# sensor_v20.net
KiCad netlist of a schematic drawn in EAGLE
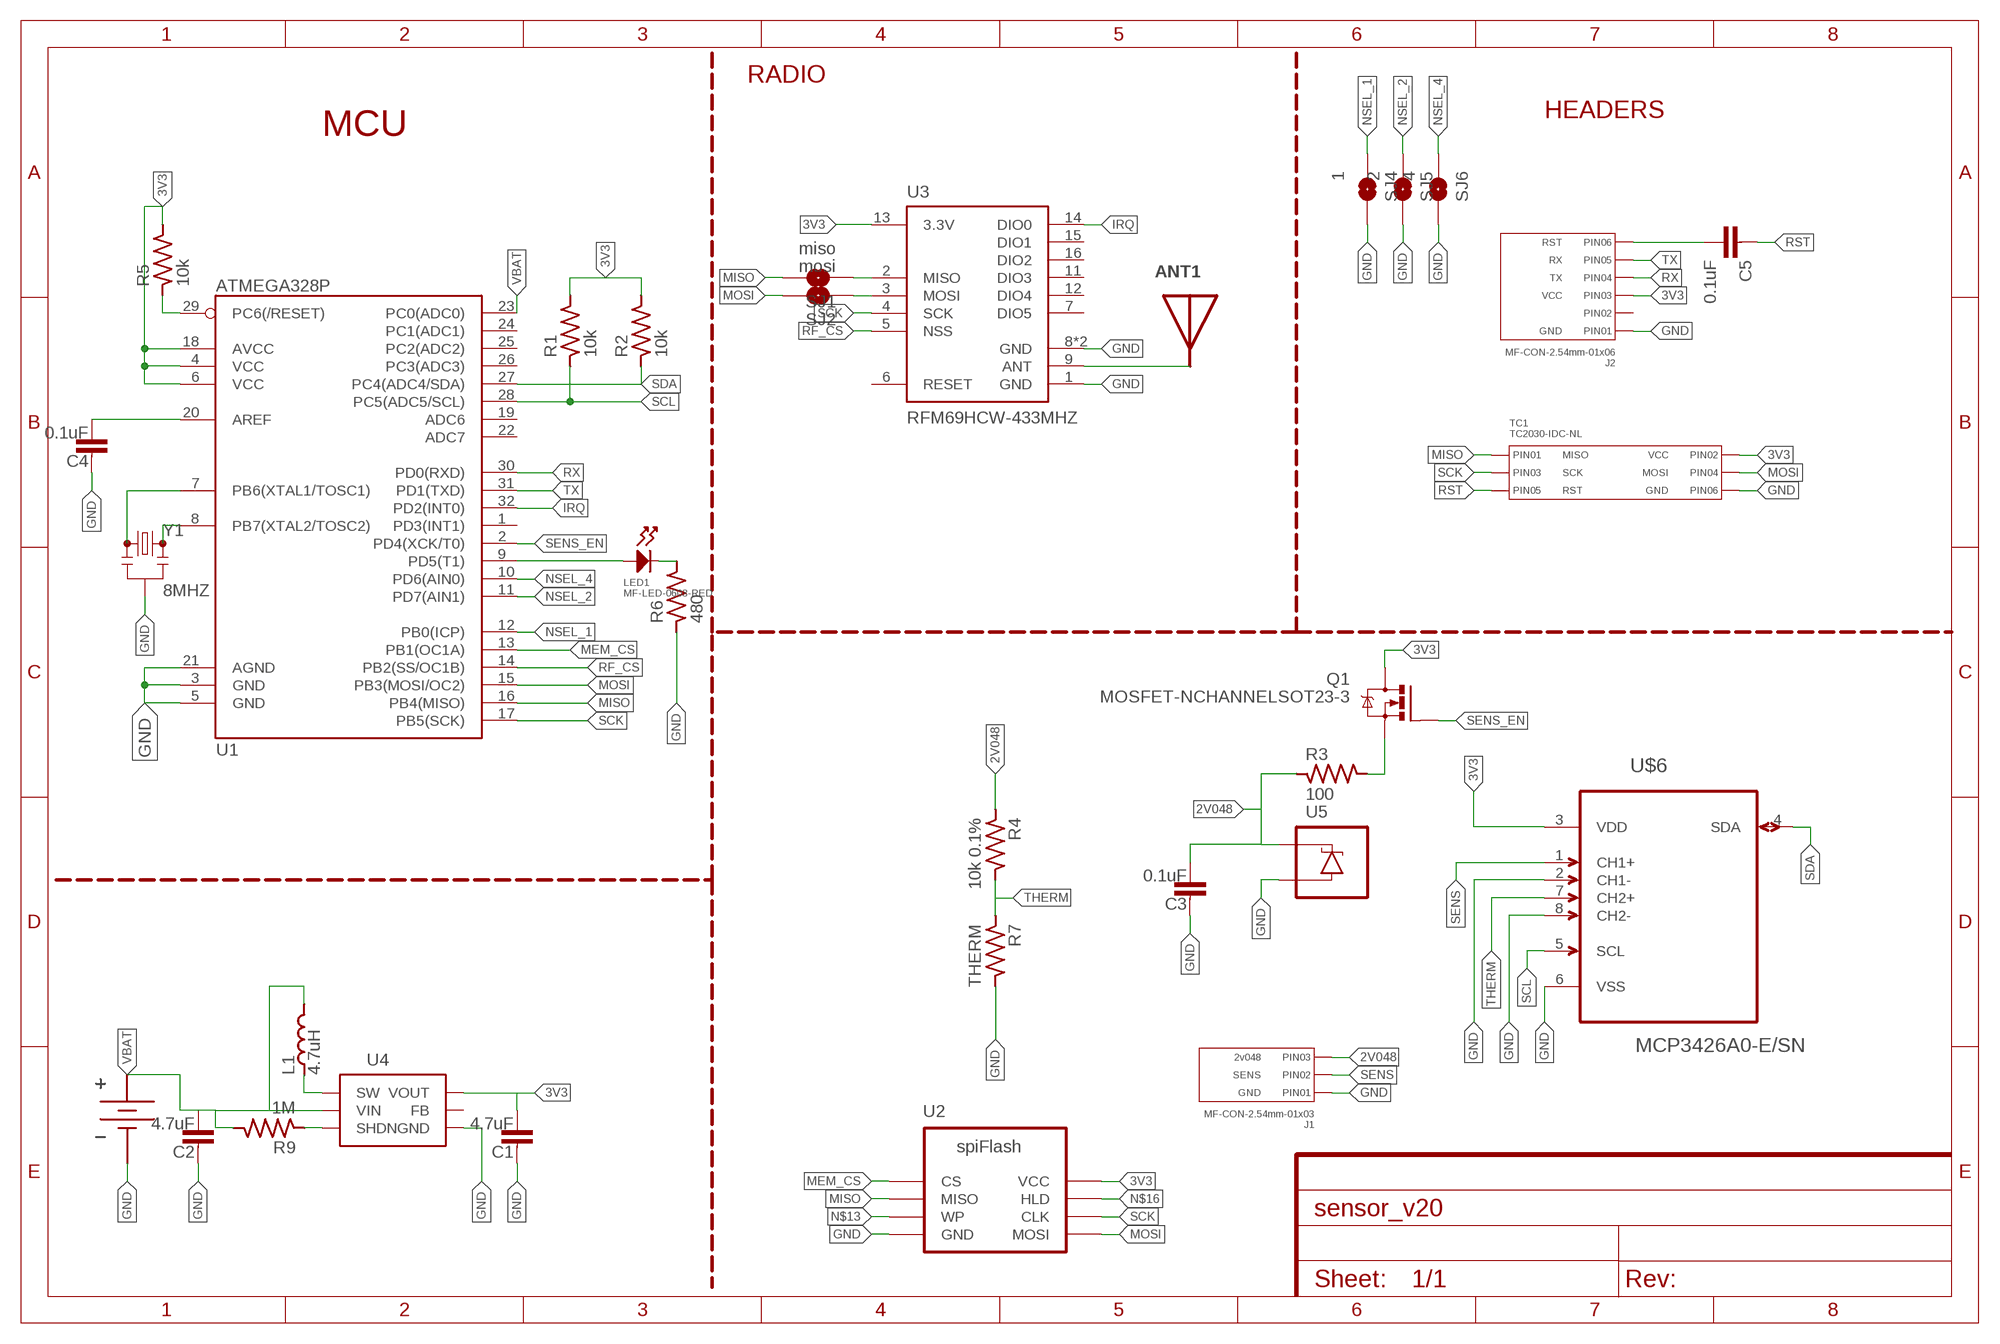
[diagram p0: schematic, sheet 1]

(export (version "E")
  (design (tool "Eeschema 10.0.6"))
  (components
    (comp (ref "ANT1")
      (value "ANTENNA-433_CHIP")
      (footprint "eagle-import:ANT_433_CHIP")
      (fields (field (name "PARTNO") "0433AT62A0020E"))
      (libsource (lib "eagle-import") (part "ANTENNA-433_CHIP"))
    )
    (comp (ref "C1")
      (value "4.7uF")
      (footprint "eagle-import:C0603-N")
      (libsource (lib "eagle-import") (part "CAPACITOR_NP0603-N"))
    )
    (comp (ref "C2")
      (value "4.7uF")
      (footprint "eagle-import:C0603-N")
      (libsource (lib "eagle-import") (part "CAPACITOR_NP0603-N"))
    )
    (comp (ref "C3")
      (value "0.1uF")
      (footprint "eagle-import:C0603-N")
      (libsource (lib "eagle-import") (part "CAPACITOR_NP0603-N"))
    )
    (comp (ref "C4")
      (value "0.1uF")
      (footprint "eagle-import:C0603-N")
      (libsource (lib "eagle-import") (part "CAPACITOR_NP0603-N"))
    )
    (comp (ref "C5")
      (value "0.1uF")
      (footprint "eagle-import:C0603-N")
      (libsource (lib "eagle-import") (part "CAPACITOR0603-N"))
    )
    (comp (ref "J1")
      (value "MF-CON-2.54mm-01x03")
      (footprint "eagle-import:PTH_2.54MM_01X03")
      (fields
        (field (name "HOUSEPART") "YES")
        (field (name "LABEL01") "GND")
        (field (name "LABEL02") "SENS")
        (field (name "LABEL03") "2v048")
        (field (name "PARTNO") "0022053031")
      )
      (libsource (lib "eagle-import") (part "CON_01X03_PTH_2.54MM"))
    )
    (comp (ref "J2")
      (value "MF-CON-2.54mm-01x06")
      (footprint "eagle-import:PTH_2.54MM_01X06")
      (fields
        (field (name "HOUSEPART") "YES")
        (field (name "LABEL01") "GND")
        (field (name "LABEL03") "VCC")
        (field (name "LABEL04") "TX")
        (field (name "LABEL05") "RX")
        (field (name "LABEL06") "RST")
      )
      (libsource (lib "eagle-import") (part "CON_01X06_PTH_2.54MM"))
    )
    (comp (ref "L1")
      (value "4.7uH")
      (footprint "eagle-import:L3030")
      (libsource (lib "eagle-import") (part "INDUCTOR3030"))
    )
    (comp (ref "LED1")
      (value "MF-LED-0603-RED")
      (footprint "eagle-import:LED0603")
      (fields (field (name "HOUSEPART") "YES"))
      (libsource (lib "eagle-import") (part "LED_SINGLE-0603-RED"))
    )
    (comp (ref "Q1")
      (value "MOSFET-NCHANNELSOT23-3")
      (footprint "eagle-import:SOT23-3")
      (libsource (lib "eagle-import") (part "MOSFET-NCHANNELSOT23-3"))
    )
    (comp (ref "R1")
      (value "10k")
      (footprint "eagle-import:R0603-N")
      (libsource (lib "eagle-import") (part "RESISTOR0603-N"))
    )
    (comp (ref "R2")
      (value "10k")
      (footprint "eagle-import:R0603-N")
      (libsource (lib "eagle-import") (part "RESISTOR0603-N"))
    )
    (comp (ref "R3")
      (value "100")
      (footprint "eagle-import:R0603-N")
      (libsource (lib "eagle-import") (part "RESISTOR0603-N"))
    )
    (comp (ref "R4")
      (value "10k 0.1%")
      (footprint "eagle-import:R0603-N")
      (fields (field (name "PARTNO") "0.1% !!"))
      (libsource (lib "eagle-import") (part "RESISTOR0603-N"))
    )
    (comp (ref "R5")
      (value "10k")
      (footprint "eagle-import:R0603-N")
      (libsource (lib "eagle-import") (part "RESISTOR0603-N"))
    )
    (comp (ref "R6")
      (value "480")
      (footprint "eagle-import:R0603-N")
      (libsource (lib "eagle-import") (part "RESISTOR0603-N"))
    )
    (comp (ref "R7")
      (value "THERM")
      (footprint "eagle-import:R0603-N")
      (fields (field (name "PARTNO") "FIND PART!!"))
      (libsource (lib "eagle-import") (part "RESISTOR0603-N"))
    )
    (comp (ref "R9")
      (value "1M")
      (footprint "eagle-import:R0603-N")
      (libsource (lib "eagle-import") (part "RESISTOR0603-N"))
    )
    (comp (ref "SJ1")
      (value "miso")
      (footprint "eagle-import:SJ_2S-NOTRACE")
      (libsource (lib "eagle-import") (part "SOLDERJUMPERNC2"))
    )
    (comp (ref "SJ2")
      (value "mosi")
      (footprint "eagle-import:SJ_2S-NOTRACE")
      (libsource (lib "eagle-import") (part "SOLDERJUMPERNC2"))
    )
    (comp (ref "SJ4")
      (value "1")
      (footprint "eagle-import:SJ_2S-NOTRACE")
      (libsource (lib "eagle-import") (part "SOLDERJUMPERNC2"))
    )
    (comp (ref "SJ5")
      (value "2")
      (footprint "eagle-import:SJ_2S-NOTRACE")
      (libsource (lib "eagle-import") (part "SOLDERJUMPERNC2"))
    )
    (comp (ref "SJ6")
      (value "4")
      (footprint "eagle-import:SJ_2S-NOTRACE")
      (libsource (lib "eagle-import") (part "SOLDERJUMPERNC2"))
    )
    (comp (ref "TC1")
      (value "TC2030-IDC-NL")
      (footprint "eagle-import:TC2030-IDC-NL")
      (fields (field (name "HOUSEPART") "NO") (field (name "PARTNO") "NA"))
      (libsource (lib "eagle-import") (part "CON_02X03_TC2030-IDC-NL_AVRISP"))
    )
    (comp (ref "U$1")
      (value "KEYSTONEAAHOLDER_2CELL")
      (footprint "eagle-import:KEYSTONEAAHOLDER_2CELL")
      (libsource (lib "eagle-import") (part "KEYSTONEAAHOLDER_2CELL"))
    )
    (comp (ref "U$6")
      (value "MCP3426A0-E/SN")
      (footprint "eagle-import:SOIC127P600X175-8N")
      (libsource (lib "eagle-import") (part "MCP3426A0-E/SN"))
    )
    (comp (ref "U1")
      (value "ATMEGA328P")
      (footprint "eagle-import:TQFP32")
      (libsource (lib "eagle-import") (part "ATMEGA328P_SMD-AU"))
    )
    (comp (ref "U2")
      (value "WINBOND_FLASH_4MBIT-SOIC")
      (footprint "eagle-import:SOIC8")
      (libsource (lib "eagle-import") (part "WINBOND_FLASH_4MBIT-SOIC"))
    )
    (comp (ref "U3")
      (value "RFM69HCW-433MHZ")
      (footprint "eagle-import:RFM69HCW-XXXS2")
      (fields (field (name "PARTNO") "COM-13910"))
      (libsource (lib "eagle-import") (part "RFM69HCW-433MHZ"))
    )
    (comp (ref "U4")
      (value "AAT1217-SOT23-6")
      (footprint "eagle-import:SOT23-6")
      (fields (field (name "PARTNO") "AAT1217ICA-3.3-T1"))
      (libsource (lib "eagle-import") (part "AAT1217-SOT23-6"))
    )
    (comp (ref "U5")
      (value "LM4040-SOT-23-3")
      (footprint "eagle-import:SOT23-3")
      (fields (field (name "PARTNO") "LM4040AIM3-2.0/NOPB "))
      (libsource (lib "eagle-import") (part "LM4040-SOT-23-3"))
    )
    (comp (ref "Y1")
      (value "8MHZ")
      (footprint "eagle-import:RESONATOR-SMD")
      (fields (field (name "PARTNO") "CSTCE8M00G55-R0"))
      (libsource (lib "eagle-import") (part "RESONATOR8MHZ"))
    )
  )
  (nets
    (net (code "1") (name "2V048") (class "Default")
      (node (ref "C3") (pin "2") (pinfunction "2_2") (pintype "passive"))
      (node (ref "J1") (pin "P$3") (pinfunction "PIN3_P$3") (pintype "bidirectional"))
      (node (ref "R3") (pin "1") (pinfunction "P$1_1") (pintype "passive"))
      (node (ref "R4") (pin "1") (pinfunction "P$1_1") (pintype "passive"))
      (node (ref "U5") (pin "1") (pinfunction "C_1") (pintype "bidirectional"))
    )
    (net (code "2") (name "3V3") (class "Default")
      (node (ref "C1") (pin "2") (pinfunction "2_2") (pintype "passive"))
      (node (ref "J2") (pin "P$3") (pinfunction "PIN3_P$3") (pintype "bidirectional"))
      (node (ref "Q1") (pin "3") (pinfunction "D_3") (pintype "passive"))
      (node (ref "R1") (pin "2") (pinfunction "P$2_2") (pintype "passive"))
      (node (ref "R2") (pin "2") (pinfunction "P$2_2") (pintype "passive"))
      (node (ref "R5") (pin "2") (pinfunction "P$2_2") (pintype "passive"))
      (node (ref "TC1") (pin "P$2") (pinfunction "PIN2_P$2") (pintype "bidirectional"))
      (node (ref "U$6") (pin "3") (pinfunction "VDD_3") (pintype "power_in"))
      (node (ref "U1") (pin "18") (pinfunction "AVCC_18") (pintype "bidirectional"))
      (node (ref "U1") (pin "4") (pinfunction "VCC_4") (pintype "bidirectional"))
      (node (ref "U1") (pin "6") (pinfunction "VCC_6") (pintype "bidirectional"))
      (node (ref "U2") (pin "8") (pinfunction "VCC_8") (pintype "bidirectional"))
      (node (ref "U3") (pin "13") (pinfunction "3.3V_13") (pintype "power_in"))
      (node (ref "U4") (pin "5") (pinfunction "VOUT_5") (pintype "bidirectional"))
    )
    (net (code "3") (name "GND") (class "Default")
      (node (ref "C1") (pin "1") (pinfunction "1_1") (pintype "passive"))
      (node (ref "C2") (pin "1") (pinfunction "1_1") (pintype "passive"))
      (node (ref "C3") (pin "1") (pinfunction "1_1") (pintype "passive"))
      (node (ref "C4") (pin "1") (pinfunction "1_1") (pintype "passive"))
      (node (ref "J1") (pin "P$1") (pinfunction "PIN1_P$1") (pintype "bidirectional"))
      (node (ref "J2") (pin "P$1") (pinfunction "PIN1_P$1") (pintype "bidirectional"))
      (node (ref "R6") (pin "1") (pinfunction "P$1_1") (pintype "passive"))
      (node (ref "R7") (pin "2") (pinfunction "P$2_2") (pintype "passive"))
      (node (ref "SJ4") (pin "2") (pinfunction "2_2") (pintype "passive"))
      (node (ref "SJ5") (pin "2") (pinfunction "2_2") (pintype "passive"))
      (node (ref "SJ6") (pin "2") (pinfunction "2_2") (pintype "passive"))
      (node (ref "TC1") (pin "P$6") (pinfunction "PIN6_P$6") (pintype "bidirectional"))
      (node (ref "U$1") (pin "P$2") (pinfunction "GND_P$2") (pintype "bidirectional"))
      (node (ref "U$6") (pin "2") (pinfunction "CH1-_2") (pintype "input"))
      (node (ref "U$6") (pin "6") (pinfunction "VSS_6") (pintype "power_in"))
      (node (ref "U$6") (pin "8") (pinfunction "CH2-_8") (pintype "input"))
      (node (ref "U1") (pin "21") (pinfunction "AGND_21") (pintype "bidirectional"))
      (node (ref "U1") (pin "3") (pinfunction "GND_3") (pintype "bidirectional"))
      (node (ref "U1") (pin "5") (pinfunction "GND_5") (pintype "bidirectional"))
      (node (ref "U2") (pin "4") (pinfunction "GND_4") (pintype "bidirectional"))
      (node (ref "U3") (pin "1") (pinfunction "GND_1") (pintype "power_in"))
      (node (ref "U3") (pin "10") (pinfunction "GND_10") (pintype "power_in"))
      (node (ref "U3") (pin "8") (pinfunction "GND_8") (pintype "power_in"))
      (node (ref "U4") (pin "2") (pinfunction "GND_2") (pintype "bidirectional"))
      (node (ref "U5") (pin "2") (pinfunction "A_2") (pintype "bidirectional"))
      (node (ref "Y1") (pin "2") (pinfunction "2_2") (pintype "passive"))
    )
    (net (code "4") (name "IRQ") (class "Default")
      (node (ref "U1") (pin "32") (pinfunction "PD2(INT0)_32") (pintype "bidirectional"))
      (node (ref "U3") (pin "14") (pinfunction "DIO0_14") (pintype "bidirectional"))
    )
    (net (code "5") (name "MEM_CS") (class "Default")
      (node (ref "U1") (pin "13") (pinfunction "PB1(OC1A)_13") (pintype "bidirectional"))
      (node (ref "U2") (pin "1") (pinfunction "CS_1") (pintype "bidirectional"))
    )
    (net (code "6") (name "MISO") (class "Default")
      (node (ref "SJ1") (pin "2") (pinfunction "2_2") (pintype "passive"))
      (node (ref "TC1") (pin "P$1") (pinfunction "PIN1_P$1") (pintype "bidirectional"))
      (node (ref "U1") (pin "16") (pinfunction "PB4(MISO)_16") (pintype "bidirectional"))
      (node (ref "U2") (pin "2") (pinfunction "MISO_2") (pintype "bidirectional"))
    )
    (net (code "7") (name "MOSI") (class "Default")
      (node (ref "SJ2") (pin "2") (pinfunction "2_2") (pintype "passive"))
      (node (ref "TC1") (pin "P$4") (pinfunction "PIN4_P$4") (pintype "bidirectional"))
      (node (ref "U1") (pin "15") (pinfunction "PB3(MOSI/OC2)_15") (pintype "bidirectional"))
      (node (ref "U2") (pin "5") (pinfunction "MOSI_5") (pintype "bidirectional"))
    )
    (net (code "8") (name "N$13") (class "Default")
      (node (ref "U2") (pin "3") (pinfunction "WP_3") (pintype "bidirectional"))
    )
    (net (code "9") (name "N$16") (class "Default")
      (node (ref "U2") (pin "7") (pinfunction "HLD_7") (pintype "bidirectional"))
    )
    (net (code "10") (name "NSEL_1") (class "Default")
      (node (ref "SJ4") (pin "1") (pinfunction "1_1") (pintype "passive"))
      (node (ref "U1") (pin "12") (pinfunction "PB0(ICP)_12") (pintype "bidirectional"))
    )
    (net (code "11") (name "NSEL_2") (class "Default")
      (node (ref "SJ5") (pin "1") (pinfunction "1_1") (pintype "passive"))
      (node (ref "U1") (pin "11") (pinfunction "PD7(AIN1)_11") (pintype "bidirectional"))
    )
    (net (code "12") (name "NSEL_4") (class "Default")
      (node (ref "SJ6") (pin "1") (pinfunction "1_1") (pintype "passive"))
      (node (ref "U1") (pin "10") (pinfunction "PD6(AIN0)_10") (pintype "bidirectional"))
    )
    (net (code "13") (name "Net-(J2-PIN6)") (class "Default")
      (node (ref "C5") (pin "2") (pinfunction "2_2") (pintype "passive"))
      (node (ref "J2") (pin "P$6") (pinfunction "PIN6_P$6") (pintype "bidirectional"))
    )
    (net (code "14") (name "Net-(Q1-S)") (class "Default")
      (node (ref "Q1") (pin "2") (pinfunction "S_2") (pintype "passive"))
      (node (ref "R3") (pin "2") (pinfunction "P$2_2") (pintype "passive"))
    )
    (net (code "15") (name "Net-(R6-P$2)") (class "Default")
      (node (ref "LED1") (pin "CATHODE") (pinfunction "CATHODE_CATHODE") (pintype "power_in"))
      (node (ref "R6") (pin "2") (pinfunction "P$2_2") (pintype "passive"))
    )
    (net (code "16") (name "Net-(R9-P$1)") (class "Default")
      (node (ref "R9") (pin "1") (pinfunction "P$1_1") (pintype "passive"))
      (node (ref "U4") (pin "4") (pinfunction "SHDN_4") (pintype "bidirectional"))
    )
    (net (code "17") (name "Net-(U1-AREF)") (class "Default")
      (node (ref "C4") (pin "2") (pinfunction "2_2") (pintype "passive"))
      (node (ref "U1") (pin "20") (pinfunction "AREF_20") (pintype "bidirectional"))
    )
    (net (code "18") (name "Net-(U1-PB6(XTAL1{slash}TOSC1))") (class "Default")
      (node (ref "U1") (pin "7") (pinfunction "PB6(XTAL1/TOSC1)_7") (pintype "bidirectional"))
      (node (ref "Y1") (pin "1") (pinfunction "1_1") (pintype "passive"))
    )
    (net (code "19") (name "Net-(U1-PB7(XTAL2{slash}TOSC2))") (class "Default")
      (node (ref "U1") (pin "8") (pinfunction "PB7(XTAL2/TOSC2)_8") (pintype "bidirectional"))
      (node (ref "Y1") (pin "3") (pinfunction "3_3") (pintype "passive"))
    )
    (net (code "20") (name "Net-(U1-PD5(T1))") (class "Default")
      (node (ref "LED1") (pin "ANODE") (pinfunction "ANODE_ANODE") (pintype "power_in"))
      (node (ref "U1") (pin "9") (pinfunction "PD5(T1)_9") (pintype "bidirectional"))
    )
    (net (code "21") (name "Net-(U3-ANT)") (class "Default")
      (node (ref "ANT1") (pin "1") (pinfunction "1_1") (pintype "bidirectional"))
      (node (ref "U3") (pin "9") (pinfunction "ANT_9") (pintype "passive"))
    )
    (net (code "22") (name "Net-(U3-MISO)") (class "Default")
      (node (ref "SJ1") (pin "1") (pinfunction "1_1") (pintype "passive"))
      (node (ref "U3") (pin "2") (pinfunction "MISO_2") (pintype "bidirectional"))
    )
    (net (code "23") (name "Net-(U3-MOSI)") (class "Default")
      (node (ref "SJ2") (pin "1") (pinfunction "1_1") (pintype "passive"))
      (node (ref "U3") (pin "3") (pinfunction "MOSI_3") (pintype "input"))
    )
    (net (code "24") (name "Net-(U4-SW)") (class "Default")
      (node (ref "L1") (pin "P$1") (pinfunction "P$1_P$1") (pintype "passive"))
      (node (ref "U4") (pin "1") (pinfunction "SW_1") (pintype "bidirectional"))
    )
    (net (code "25") (name "RF_CS") (class "Default")
      (node (ref "U1") (pin "14") (pinfunction "PB2(SS/OC1B)_14") (pintype "bidirectional"))
      (node (ref "U3") (pin "5") (pinfunction "NSS_5") (pintype "input"))
    )
    (net (code "26") (name "RST") (class "Default")
      (node (ref "C5") (pin "1") (pinfunction "1_1") (pintype "passive"))
      (node (ref "R5") (pin "1") (pinfunction "P$1_1") (pintype "passive"))
      (node (ref "TC1") (pin "P$5") (pinfunction "PIN5_P$5") (pintype "bidirectional"))
      (node (ref "U1") (pin "29") (pinfunction "PC6(/RESET)_29") (pintype "bidirectional"))
    )
    (net (code "27") (name "RX") (class "Default")
      (node (ref "J2") (pin "P$4") (pinfunction "PIN4_P$4") (pintype "bidirectional"))
      (node (ref "U1") (pin "30") (pinfunction "PD0(RXD)_30") (pintype "bidirectional"))
    )
    (net (code "28") (name "SCK") (class "Default")
      (node (ref "TC1") (pin "P$3") (pinfunction "PIN3_P$3") (pintype "bidirectional"))
      (node (ref "U1") (pin "17") (pinfunction "PB5(SCK)_17") (pintype "bidirectional"))
      (node (ref "U2") (pin "6") (pinfunction "CLK_6") (pintype "bidirectional"))
      (node (ref "U3") (pin "4") (pinfunction "SCK_4") (pintype "input"))
    )
    (net (code "29") (name "SCL") (class "Default")
      (node (ref "R1") (pin "1") (pinfunction "P$1_1") (pintype "passive"))
      (node (ref "U$6") (pin "5") (pinfunction "SCL_5") (pintype "input"))
      (node (ref "U1") (pin "28") (pinfunction "PC5(ADC5/SCL)_28") (pintype "bidirectional"))
    )
    (net (code "30") (name "SDA") (class "Default")
      (node (ref "R2") (pin "1") (pinfunction "P$1_1") (pintype "passive"))
      (node (ref "U$6") (pin "4") (pinfunction "SDA_4") (pintype "bidirectional"))
      (node (ref "U1") (pin "27") (pinfunction "PC4(ADC4/SDA)_27") (pintype "bidirectional"))
    )
    (net (code "31") (name "SENS") (class "Default")
      (node (ref "J1") (pin "P$2") (pinfunction "PIN2_P$2") (pintype "bidirectional"))
      (node (ref "U$6") (pin "1") (pinfunction "CH1+_1") (pintype "input"))
    )
    (net (code "32") (name "SENS_EN") (class "Default")
      (node (ref "Q1") (pin "1") (pinfunction "G_1") (pintype "passive"))
      (node (ref "U1") (pin "2") (pinfunction "PD4(XCK/T0)_2") (pintype "bidirectional"))
    )
    (net (code "33") (name "THERM") (class "Default")
      (node (ref "R4") (pin "2") (pinfunction "P$2_2") (pintype "passive"))
      (node (ref "R7") (pin "1") (pinfunction "P$1_1") (pintype "passive"))
      (node (ref "U$6") (pin "7") (pinfunction "CH2+_7") (pintype "input"))
    )
    (net (code "34") (name "TX") (class "Default")
      (node (ref "J2") (pin "P$5") (pinfunction "PIN5_P$5") (pintype "bidirectional"))
      (node (ref "U1") (pin "31") (pinfunction "PD1(TXD)_31") (pintype "bidirectional"))
    )
    (net (code "35") (name "VBAT") (class "Default")
      (node (ref "C2") (pin "2") (pinfunction "2_2") (pintype "passive"))
      (node (ref "L1") (pin "P$2") (pinfunction "P$2_P$2") (pintype "passive"))
      (node (ref "R9") (pin "2") (pinfunction "P$2_2") (pintype "passive"))
      (node (ref "U$1") (pin "P$1") (pinfunction "VBAT_P$1") (pintype "bidirectional"))
      (node (ref "U1") (pin "23") (pinfunction "PC0(ADC0)_23") (pintype "bidirectional"))
      (node (ref "U4") (pin "6") (pinfunction "VIN_6") (pintype "bidirectional"))
    )
    (net (code "36") (name "unconnected-(J2-PIN2-PadP$2)") (class "Default")
      (node (ref "J2") (pin "P$2") (pinfunction "PIN2_P$2") (pintype "bidirectional"))
    )
    (net (code "37") (name "unconnected-(U1-ADC6-Pad19)") (class "Default")
      (node (ref "U1") (pin "19") (pinfunction "ADC6_19") (pintype "bidirectional"))
    )
    (net (code "38") (name "unconnected-(U1-ADC7-Pad22)") (class "Default")
      (node (ref "U1") (pin "22") (pinfunction "ADC7_22") (pintype "bidirectional"))
    )
    (net (code "39") (name "unconnected-(U1-PC1(ADC1)-Pad24)") (class "Default")
      (node (ref "U1") (pin "24") (pinfunction "PC1(ADC1)_24") (pintype "bidirectional"))
    )
    (net (code "40") (name "unconnected-(U1-PC2(ADC2)-Pad25)") (class "Default")
      (node (ref "U1") (pin "25") (pinfunction "PC2(ADC2)_25") (pintype "bidirectional"))
    )
    (net (code "41") (name "unconnected-(U1-PC3(ADC3)-Pad26)") (class "Default")
      (node (ref "U1") (pin "26") (pinfunction "PC3(ADC3)_26") (pintype "bidirectional"))
    )
    (net (code "42") (name "unconnected-(U1-PD3(INT1)-Pad1)") (class "Default")
      (node (ref "U1") (pin "1") (pinfunction "PD3(INT1)_1") (pintype "bidirectional"))
    )
    (net (code "43") (name "unconnected-(U3-DIO1-Pad15)") (class "Default")
      (node (ref "U3") (pin "15") (pinfunction "DIO1_15") (pintype "bidirectional"))
    )
    (net (code "44") (name "unconnected-(U3-DIO2-Pad16)") (class "Default")
      (node (ref "U3") (pin "16") (pinfunction "DIO2_16") (pintype "bidirectional"))
    )
    (net (code "45") (name "unconnected-(U3-DIO3-Pad11)") (class "Default")
      (node (ref "U3") (pin "11") (pinfunction "DIO3_11") (pintype "bidirectional"))
    )
    (net (code "46") (name "unconnected-(U3-DIO4-Pad12)") (class "Default")
      (node (ref "U3") (pin "12") (pinfunction "DIO4_12") (pintype "bidirectional"))
    )
    (net (code "47") (name "unconnected-(U3-DIO5-Pad7)") (class "Default")
      (node (ref "U3") (pin "7") (pinfunction "DIO5_7") (pintype "bidirectional"))
    )
    (net (code "48") (name "unconnected-(U3-RESET-Pad6)") (class "Default")
      (node (ref "U3") (pin "6") (pinfunction "RESET_6") (pintype "input"))
    )
    (net (code "49") (name "unconnected-(U4-FB-Pad3)") (class "Default")
      (node (ref "U4") (pin "3") (pinfunction "FB_3") (pintype "bidirectional"))
    )
  )
)
